# schematics.net
KiCad netlist of a schematic drawn in EasyEDA
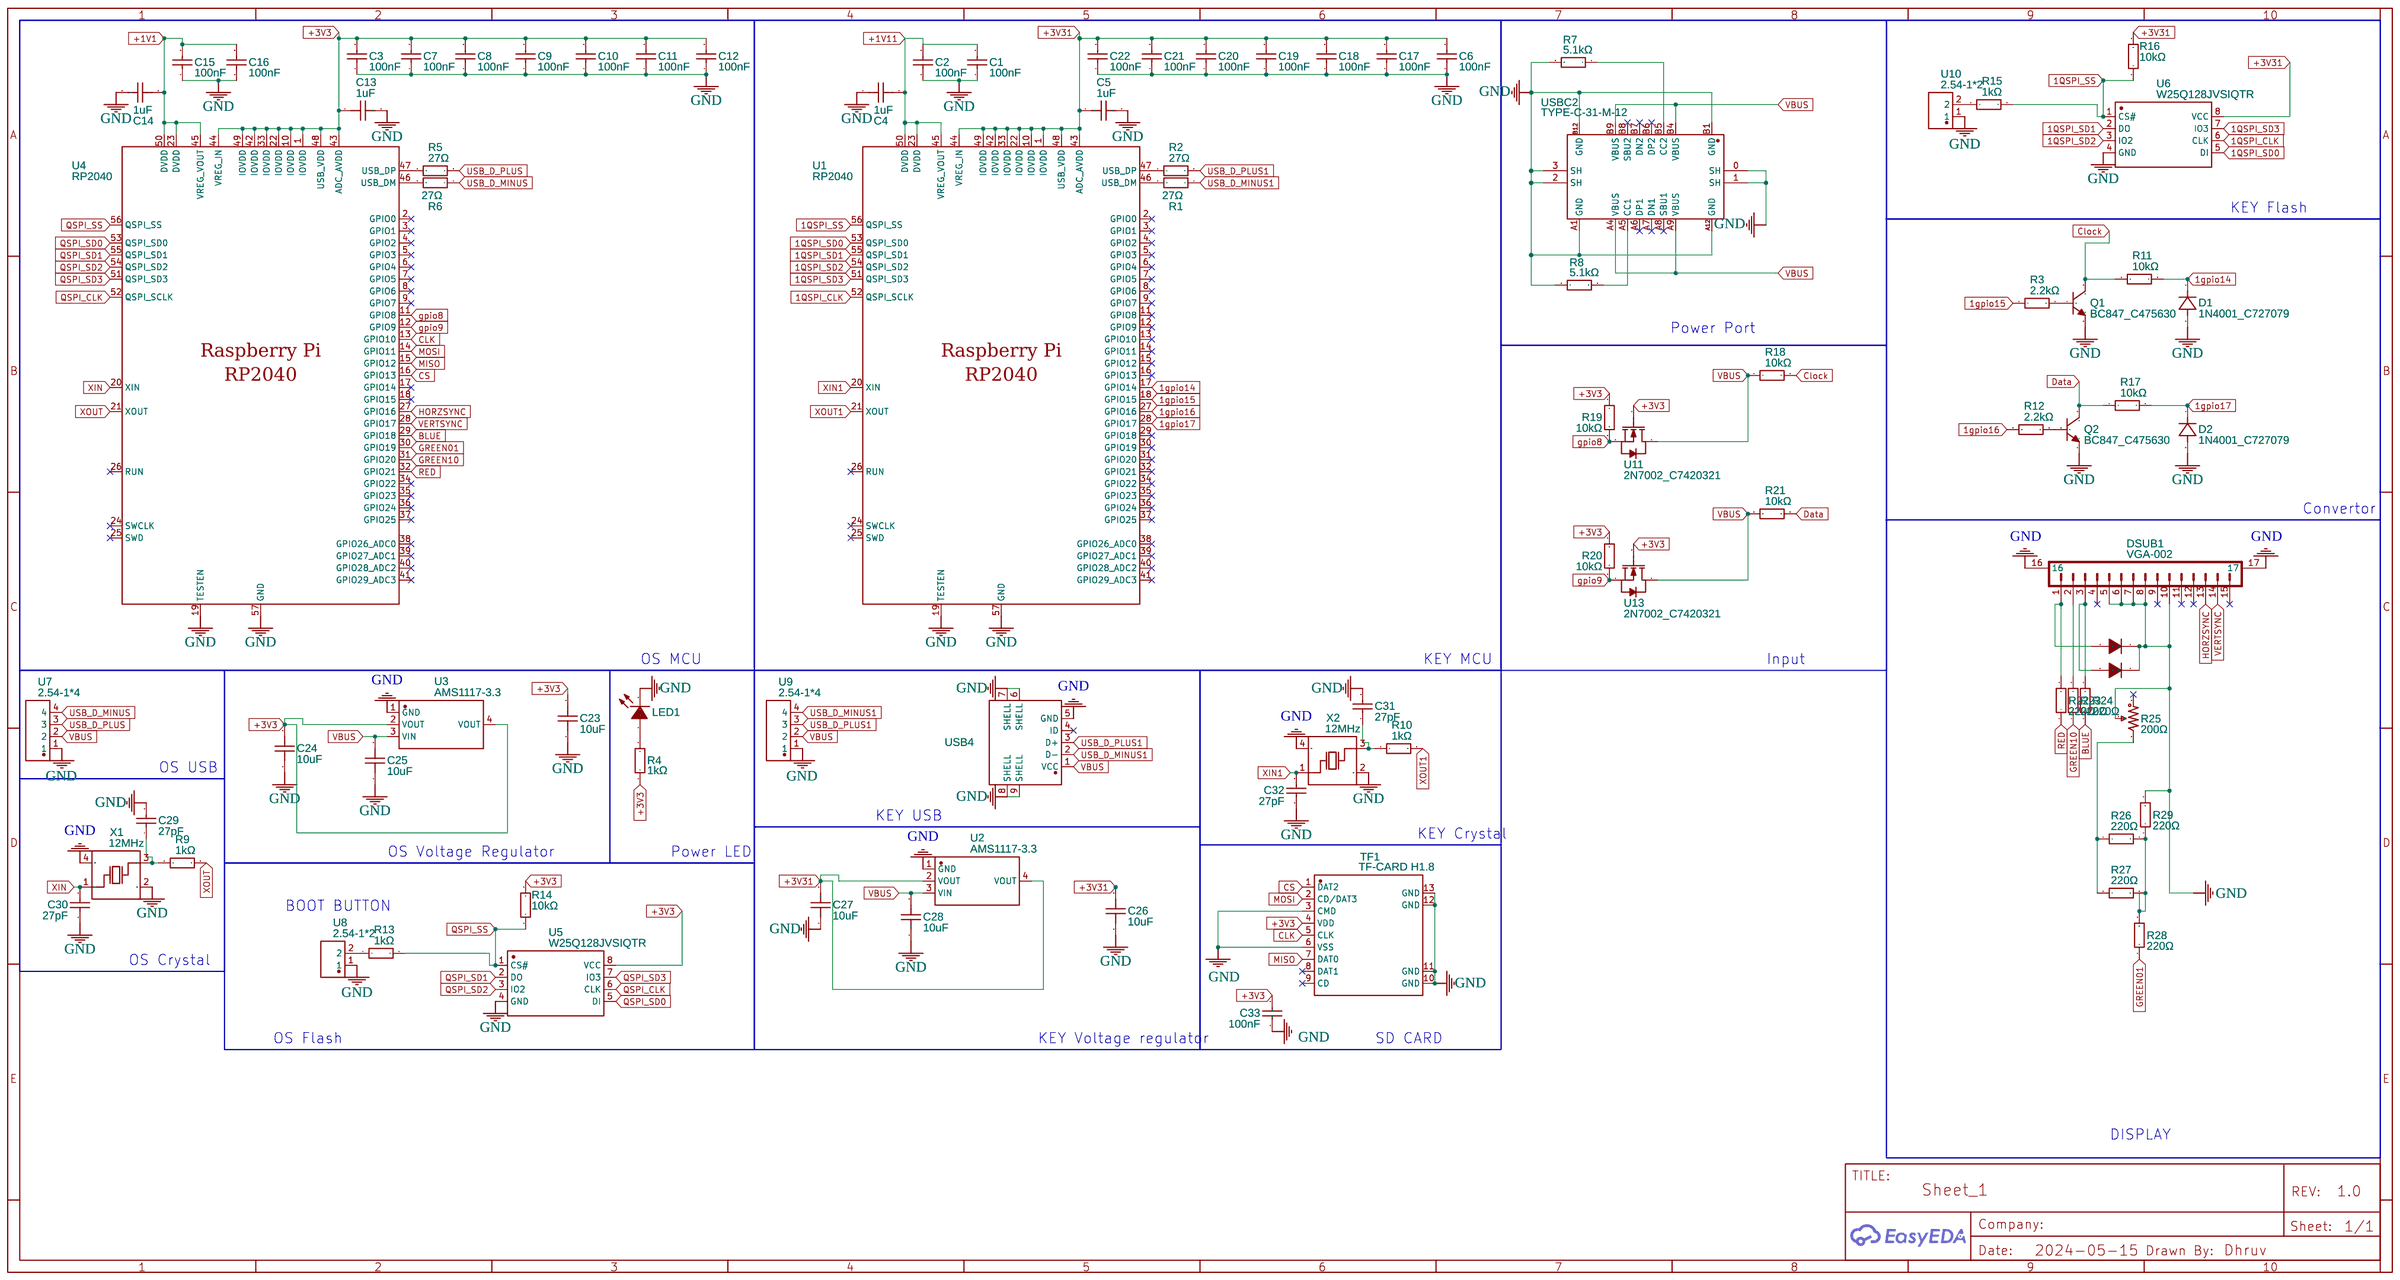
[diagram p0: schematic sheet]

(export (version "E")
  (design (tool "Eeschema 10.0.6"))
  (components
    (comp (ref "C1")
      (value "100nF")
      (fields
        (field (name "Manufacturer Part") "CL05B104KO5NNNC")
        (field (name "Manufacturer") "SAMSUNG(三星)")
      )
      (libsource (lib "") (part "CL05B104KO5NNNC_1"))
    )
    (comp (ref "C2")
      (value "100nF")
      (fields
        (field (name "Manufacturer Part") "CL05B104KO5NNNC")
        (field (name "Manufacturer") "SAMSUNG(三星)")
      )
      (libsource (lib "") (part "CL05B104KO5NNNC_1"))
    )
    (comp (ref "C3")
      (value "100nF")
      (fields
        (field (name "Manufacturer Part") "CL05B104KO5NNNC")
        (field (name "Manufacturer") "SAMSUNG(三星)")
      )
      (libsource (lib "") (part "CL05B104KO5NNNC_1"))
    )
    (comp (ref "C4")
      (value "1uF")
      (fields
        (field (name "Manufacturer Part") "CL05A105KA5NQNC")
        (field (name "Manufacturer") "SAMSUNG(三星)")
      )
      (libsource (lib "") (part "CL05A105KA5NQNC_1"))
    )
    (comp (ref "C5")
      (value "1uF")
      (fields
        (field (name "Manufacturer Part") "CL05A105KA5NQNC")
        (field (name "Manufacturer") "SAMSUNG(三星)")
      )
      (libsource (lib "") (part "CL05A105KA5NQNC"))
    )
    (comp (ref "C6")
      (value "100nF")
      (fields
        (field (name "Manufacturer Part") "CL05B104KO5NNNC")
        (field (name "Manufacturer") "SAMSUNG(三星)")
      )
      (libsource (lib "") (part "CL05B104KO5NNNC_1"))
    )
    (comp (ref "C7")
      (value "100nF")
      (fields
        (field (name "Manufacturer Part") "CL05B104KO5NNNC")
        (field (name "Manufacturer") "SAMSUNG(三星)")
      )
      (libsource (lib "") (part "CL05B104KO5NNNC_1"))
    )
    (comp (ref "C8")
      (value "100nF")
      (fields
        (field (name "Manufacturer Part") "CL05B104KO5NNNC")
        (field (name "Manufacturer") "SAMSUNG(三星)")
      )
      (libsource (lib "") (part "CL05B104KO5NNNC_1"))
    )
    (comp (ref "C9")
      (value "100nF")
      (fields
        (field (name "Manufacturer Part") "CL05B104KO5NNNC")
        (field (name "Manufacturer") "SAMSUNG(三星)")
      )
      (libsource (lib "") (part "CL05B104KO5NNNC_1"))
    )
    (comp (ref "C10")
      (value "100nF")
      (fields
        (field (name "Manufacturer Part") "CL05B104KO5NNNC")
        (field (name "Manufacturer") "SAMSUNG(三星)")
      )
      (libsource (lib "") (part "CL05B104KO5NNNC_1"))
    )
    (comp (ref "C11")
      (value "100nF")
      (fields
        (field (name "Manufacturer Part") "CL05B104KO5NNNC")
        (field (name "Manufacturer") "SAMSUNG(三星)")
      )
      (libsource (lib "") (part "CL05B104KO5NNNC_1"))
    )
    (comp (ref "C12")
      (value "100nF")
      (fields
        (field (name "Manufacturer Part") "CL05B104KO5NNNC")
        (field (name "Manufacturer") "SAMSUNG(三星)")
      )
      (libsource (lib "") (part "CL05B104KO5NNNC_1"))
    )
    (comp (ref "C13")
      (value "1uF")
      (fields
        (field (name "Manufacturer Part") "CL05A105KA5NQNC")
        (field (name "Manufacturer") "SAMSUNG(三星)")
      )
      (libsource (lib "") (part "CL05A105KA5NQNC"))
    )
    (comp (ref "C14")
      (value "1uF")
      (fields
        (field (name "Manufacturer Part") "CL05A105KA5NQNC")
        (field (name "Manufacturer") "SAMSUNG(三星)")
      )
      (libsource (lib "") (part "CL05A105KA5NQNC_1"))
    )
    (comp (ref "C15")
      (value "100nF")
      (fields
        (field (name "Manufacturer Part") "CL05B104KO5NNNC")
        (field (name "Manufacturer") "SAMSUNG(三星)")
      )
      (libsource (lib "") (part "CL05B104KO5NNNC_1"))
    )
    (comp (ref "C16")
      (value "100nF")
      (fields
        (field (name "Manufacturer Part") "CL05B104KO5NNNC")
        (field (name "Manufacturer") "SAMSUNG(三星)")
      )
      (libsource (lib "") (part "CL05B104KO5NNNC_1"))
    )
    (comp (ref "C17")
      (value "100nF")
      (fields
        (field (name "Manufacturer Part") "CL05B104KO5NNNC")
        (field (name "Manufacturer") "SAMSUNG(三星)")
      )
      (libsource (lib "") (part "CL05B104KO5NNNC_1"))
    )
    (comp (ref "C18")
      (value "100nF")
      (fields
        (field (name "Manufacturer Part") "CL05B104KO5NNNC")
        (field (name "Manufacturer") "SAMSUNG(三星)")
      )
      (libsource (lib "") (part "CL05B104KO5NNNC_1"))
    )
    (comp (ref "C19")
      (value "100nF")
      (fields
        (field (name "Manufacturer Part") "CL05B104KO5NNNC")
        (field (name "Manufacturer") "SAMSUNG(三星)")
      )
      (libsource (lib "") (part "CL05B104KO5NNNC_1"))
    )
    (comp (ref "C20")
      (value "100nF")
      (fields
        (field (name "Manufacturer Part") "CL05B104KO5NNNC")
        (field (name "Manufacturer") "SAMSUNG(三星)")
      )
      (libsource (lib "") (part "CL05B104KO5NNNC_1"))
    )
    (comp (ref "C21")
      (value "100nF")
      (fields
        (field (name "Manufacturer Part") "CL05B104KO5NNNC")
        (field (name "Manufacturer") "SAMSUNG(三星)")
      )
      (libsource (lib "") (part "CL05B104KO5NNNC_1"))
    )
    (comp (ref "C22")
      (value "100nF")
      (fields
        (field (name "Manufacturer Part") "CL05B104KO5NNNC")
        (field (name "Manufacturer") "SAMSUNG(三星)")
      )
      (libsource (lib "") (part "CL05B104KO5NNNC_1"))
    )
    (comp (ref "C23")
      (value "10uF")
      (fields
        (field (name "Manufacturer Part") "CL10A106KP8NNNC")
        (field (name "Manufacturer") "SAMSUNG(三星)")
      )
      (libsource (lib "") (part "CL10A106KP8NNNC"))
    )
    (comp (ref "C24")
      (value "10uF")
      (fields
        (field (name "Manufacturer Part") "CL10A106KP8NNNC")
        (field (name "Manufacturer") "SAMSUNG(三星)")
      )
      (libsource (lib "") (part "CL10A106KP8NNNC"))
    )
    (comp (ref "C25")
      (value "10uF")
      (fields
        (field (name "Manufacturer Part") "CL10A106KP8NNNC")
        (field (name "Manufacturer") "SAMSUNG(三星)")
      )
      (libsource (lib "") (part "CL10A106KP8NNNC"))
    )
    (comp (ref "C26")
      (value "10uF")
      (fields
        (field (name "Manufacturer Part") "CL10A106KP8NNNC")
        (field (name "Manufacturer") "SAMSUNG(三星)")
      )
      (libsource (lib "") (part "CL10A106KP8NNNC"))
    )
    (comp (ref "C27")
      (value "10uF")
      (fields
        (field (name "Manufacturer Part") "CL10A106KP8NNNC")
        (field (name "Manufacturer") "SAMSUNG(三星)")
      )
      (libsource (lib "") (part "CL10A106KP8NNNC"))
    )
    (comp (ref "C28")
      (value "10uF")
      (fields
        (field (name "Manufacturer Part") "CL10A106KP8NNNC")
        (field (name "Manufacturer") "SAMSUNG(三星)")
      )
      (libsource (lib "") (part "CL10A106KP8NNNC"))
    )
    (comp (ref "C29")
      (value "27pF")
      (fields
        (field (name "Manufacturer Part") "CC0603JRNPO9BN270")
        (field (name "Manufacturer") "YAGEO(国巨)")
      )
      (libsource (lib "") (part "CC0603JRNPO9BN270_1"))
    )
    (comp (ref "C30")
      (value "27pF")
      (fields
        (field (name "Manufacturer Part") "CC0603JRNPO9BN270")
        (field (name "Manufacturer") "YAGEO(国巨)")
      )
      (libsource (lib "") (part "CC0603JRNPO9BN270"))
    )
    (comp (ref "C31")
      (value "27pF")
      (fields
        (field (name "Manufacturer Part") "CC0603JRNPO9BN270")
        (field (name "Manufacturer") "YAGEO(国巨)")
      )
      (libsource (lib "") (part "CC0603JRNPO9BN270_1"))
    )
    (comp (ref "C32")
      (value "27pF")
      (fields
        (field (name "Manufacturer Part") "CC0603JRNPO9BN270")
        (field (name "Manufacturer") "YAGEO(国巨)")
      )
      (libsource (lib "") (part "CC0603JRNPO9BN270"))
    )
    (comp (ref "C33")
      (value "100nF")
      (fields
        (field (name "Manufacturer Part") "CL05B104KO5NNNC")
        (field (name "Manufacturer") "SAMSUNG(三星)")
      )
      (libsource (lib "") (part "CL05B104KO5NNNC"))
    )
    (comp (ref "D1")
      (value "1N4001_C727079")
      (fields (field (name "Manufacturer Part") "1N4001") (field (name "Manufacturer") "TWGMC(台湾迪嘉)"))
      (libsource (lib "") (part "1N4001_C727079"))
    )
    (comp (ref "D2")
      (value "1N4001_C727079")
      (fields (field (name "Manufacturer Part") "1N4001") (field (name "Manufacturer") "TWGMC(台湾迪嘉)"))
      (libsource (lib "") (part "1N4001_C727079"))
    )
    (comp (ref "D3")
      (value "1N4148WS T4")
      (fields (field (name "Manufacturer Part") "1N4148WS") (field (name "Manufacturer") "CJ(江苏长电/长晶)"))
      (libsource (lib "") (part "1N4148WS T4"))
    )
    (comp (ref "D4")
      (value "1N4148WS T4")
      (fields (field (name "Manufacturer Part") "1N4148WS") (field (name "Manufacturer") "CJ(江苏长电/长晶)"))
      (libsource (lib "") (part "1N4148WS T4"))
    )
    (comp (ref "DSUB1")
      (value "VGA-002")
      (fields (field (name "Manufacturer") "BOOMELE(博穆精密)"))
      (libsource (lib "") (part "VGA-002"))
    )
    (comp (ref "LED1")
      (value "0603White light_C2290")
      (fields (field (name "Manufacturer Part") "KT-0603白灯") (field (name "Manufacturer") "KENTO"))
      (libsource (lib "") (part "0603White light_C2290"))
    )
    (comp (ref "Q1")
      (value "BC847_C475630")
      (fields (field (name "Manufacturer Part") "BC847") (field (name "Manufacturer") "SHIKUES(时科)"))
      (libsource (lib "") (part "BC847_C475630"))
    )
    (comp (ref "Q2")
      (value "BC847_C475630")
      (fields (field (name "Manufacturer Part") "BC847") (field (name "Manufacturer") "SHIKUES(时科)"))
      (libsource (lib "") (part "BC847_C475630"))
    )
    (comp (ref "R1")
      (value "27Ω")
      (fields
        (field (name "Manufacturer Part") "0805W8F270JT5E")
        (field (name "Manufacturer") "UNI-ROYAL(厚声)")
      )
      (libsource (lib "") (part "0805W8F270JT5E"))
    )
    (comp (ref "R2")
      (value "27Ω")
      (fields
        (field (name "Manufacturer Part") "0805W8F270JT5E")
        (field (name "Manufacturer") "UNI-ROYAL(厚声)")
      )
      (libsource (lib "") (part "0805W8F270JT5E_1"))
    )
    (comp (ref "R3")
      (value "2.2kΩ")
      (fields
        (field (name "Manufacturer Part") "0402WGF2201TCE")
        (field (name "Manufacturer") "UNI-ROYAL(厚声)")
      )
      (libsource (lib "") (part "0402WGF2201TCE"))
    )
    (comp (ref "R4")
      (value "1kΩ")
      (fields
        (field (name "Manufacturer Part") "0402WGF1001TCE")
        (field (name "Manufacturer") "UNI-ROYAL(厚声)")
      )
      (libsource (lib "") (part "0402WGF1001TCE_1"))
    )
    (comp (ref "R5")
      (value "27Ω")
      (fields
        (field (name "Manufacturer Part") "0805W8F270JT5E")
        (field (name "Manufacturer") "UNI-ROYAL(厚声)")
      )
      (libsource (lib "") (part "0805W8F270JT5E_1"))
    )
    (comp (ref "R6")
      (value "27Ω")
      (fields
        (field (name "Manufacturer Part") "0805W8F270JT5E")
        (field (name "Manufacturer") "UNI-ROYAL(厚声)")
      )
      (libsource (lib "") (part "0805W8F270JT5E"))
    )
    (comp (ref "R7")
      (value "5.1kΩ")
      (fields (field (name "Manufacturer Part") "RTT02512JTH") (field (name "Manufacturer") "RALEC(旺诠)"))
      (libsource (lib "") (part "RTT02512JTH_1"))
    )
    (comp (ref "R8")
      (value "5.1kΩ")
      (fields (field (name "Manufacturer Part") "RTT02512JTH") (field (name "Manufacturer") "RALEC(旺诠)"))
      (libsource (lib "") (part "RTT02512JTH"))
    )
    (comp (ref "R9")
      (value "1kΩ")
      (fields
        (field (name "Manufacturer Part") "0402WGF1001TCE")
        (field (name "Manufacturer") "UNI-ROYAL(厚声)")
      )
      (libsource (lib "") (part "0402WGF1001TCE"))
    )
    (comp (ref "R10")
      (value "1kΩ")
      (fields
        (field (name "Manufacturer Part") "0402WGF1001TCE")
        (field (name "Manufacturer") "UNI-ROYAL(厚声)")
      )
      (libsource (lib "") (part "0402WGF1001TCE"))
    )
    (comp (ref "R11")
      (value "10kΩ")
      (fields
        (field (name "Manufacturer Part") "0402WGF1002TCE")
        (field (name "Manufacturer") "UNI-ROYAL(厚声)")
      )
      (libsource (lib "") (part "0402WGF1002TCE"))
    )
    (comp (ref "R12")
      (value "2.2kΩ")
      (fields
        (field (name "Manufacturer Part") "0402WGF2201TCE")
        (field (name "Manufacturer") "UNI-ROYAL(厚声)")
      )
      (libsource (lib "") (part "0402WGF2201TCE"))
    )
    (comp (ref "R13")
      (value "1kΩ")
      (fields
        (field (name "Manufacturer Part") "0402WGF1001TCE")
        (field (name "Manufacturer") "UNI-ROYAL(厚声)")
      )
      (libsource (lib "") (part "0402WGF1001TCE"))
    )
    (comp (ref "R14")
      (value "10kΩ")
      (fields
        (field (name "Manufacturer Part") "0402WGF1002TCE")
        (field (name "Manufacturer") "UNI-ROYAL(厚声)")
      )
      (libsource (lib "") (part "0402WGF1002TCE_1"))
    )
    (comp (ref "R15")
      (value "1kΩ")
      (fields
        (field (name "Manufacturer Part") "0402WGF1001TCE")
        (field (name "Manufacturer") "UNI-ROYAL(厚声)")
      )
      (libsource (lib "") (part "0402WGF1001TCE"))
    )
    (comp (ref "R16")
      (value "10kΩ")
      (fields
        (field (name "Manufacturer Part") "0402WGF1002TCE")
        (field (name "Manufacturer") "UNI-ROYAL(厚声)")
      )
      (libsource (lib "") (part "0402WGF1002TCE_1"))
    )
    (comp (ref "R17")
      (value "10kΩ")
      (fields
        (field (name "Manufacturer Part") "0402WGF1002TCE")
        (field (name "Manufacturer") "UNI-ROYAL(厚声)")
      )
      (libsource (lib "") (part "0402WGF1002TCE"))
    )
    (comp (ref "R18")
      (value "10kΩ")
      (fields
        (field (name "Manufacturer Part") "0402WGF1002TCE")
        (field (name "Manufacturer") "UNI-ROYAL(厚声)")
      )
      (libsource (lib "") (part "0402WGF1002TCE"))
    )
    (comp (ref "R19")
      (value "10kΩ")
      (fields
        (field (name "Manufacturer Part") "0402WGF1002TCE")
        (field (name "Manufacturer") "UNI-ROYAL(厚声)")
      )
      (libsource (lib "") (part "0402WGF1002TCE_2"))
    )
    (comp (ref "R20")
      (value "10kΩ")
      (fields
        (field (name "Manufacturer Part") "0402WGF1002TCE")
        (field (name "Manufacturer") "UNI-ROYAL(厚声)")
      )
      (libsource (lib "") (part "0402WGF1002TCE_2"))
    )
    (comp (ref "R21")
      (value "10kΩ")
      (fields
        (field (name "Manufacturer Part") "0402WGF1002TCE")
        (field (name "Manufacturer") "UNI-ROYAL(厚声)")
      )
      (libsource (lib "") (part "0402WGF1002TCE"))
    )
    (comp (ref "R22")
      (value "220Ω")
      (fields
        (field (name "Manufacturer Part") "0402WGF2200TCE")
        (field (name "Manufacturer") "UNI-ROYAL(厚声)")
      )
      (libsource (lib "") (part "0402WGF2200TCE"))
    )
    (comp (ref "R23")
      (value "220Ω")
      (fields
        (field (name "Manufacturer Part") "0402WGF2200TCE")
        (field (name "Manufacturer") "UNI-ROYAL(厚声)")
      )
      (libsource (lib "") (part "0402WGF2200TCE"))
    )
    (comp (ref "R24")
      (value "220Ω")
      (fields
        (field (name "Manufacturer Part") "0402WGF2200TCE")
        (field (name "Manufacturer") "UNI-ROYAL(厚声)")
      )
      (libsource (lib "") (part "0402WGF2200TCE"))
    )
    (comp (ref "R25")
      (value "200Ω")
      (fields (field (name "Manufacturer Part") "3266W-1-201") (field (name "Manufacturer") "BOCHEN(博晨)"))
      (libsource (lib "") (part "3266W-1-201"))
    )
    (comp (ref "R26")
      (value "220Ω")
      (fields
        (field (name "Manufacturer Part") "0402WGF2200TCE")
        (field (name "Manufacturer") "UNI-ROYAL(厚声)")
      )
      (libsource (lib "") (part "0402WGF2200TCE_1"))
    )
    (comp (ref "R27")
      (value "220Ω")
      (fields
        (field (name "Manufacturer Part") "0402WGF2200TCE")
        (field (name "Manufacturer") "UNI-ROYAL(厚声)")
      )
      (libsource (lib "") (part "0402WGF2200TCE_1"))
    )
    (comp (ref "R28")
      (value "220Ω")
      (fields
        (field (name "Manufacturer Part") "0402WGF2200TCE")
        (field (name "Manufacturer") "UNI-ROYAL(厚声)")
      )
      (libsource (lib "") (part "0402WGF2200TCE"))
    )
    (comp (ref "R29")
      (value "220Ω")
      (fields
        (field (name "Manufacturer Part") "0402WGF2200TCE")
        (field (name "Manufacturer") "UNI-ROYAL(厚声)")
      )
      (libsource (lib "") (part "0402WGF2200TCE"))
    )
    (comp (ref "TF1")
      (value "TF-CARD H1.8")
      (fields (field (name "Manufacturer") "SHOU HAN(首韩)"))
      (libsource (lib "") (part "TF-CARD H1.8"))
    )
    (comp (ref "U1")
      (value "RP2040")
      (fields (field (name "Manufacturer") "Raspberry Pi(树莓派)"))
      (libsource (lib "") (part "RP2040"))
    )
    (comp (ref "U2")
      (value "AMS1117-3.3")
      (fields (field (name "Manufacturer") "AMS"))
      (libsource (lib "") (part "AMS1117-3.3"))
    )
    (comp (ref "U3")
      (value "AMS1117-3.3")
      (fields (field (name "Manufacturer") "AMS"))
      (libsource (lib "") (part "AMS1117-3.3"))
    )
    (comp (ref "U4")
      (value "RP2040")
      (fields (field (name "Manufacturer") "Raspberry Pi(树莓派)"))
      (libsource (lib "") (part "RP2040"))
    )
    (comp (ref "U5")
      (value "W25Q128JVSIQTR")
      (fields (field (name "Manufacturer Part") "W25Q128JVSIQ") (field (name "Manufacturer") "WINBOND(华邦)"))
      (libsource (lib "") (part "W25Q128JVSIQTR"))
    )
    (comp (ref "U6")
      (value "W25Q128JVSIQTR")
      (fields (field (name "Manufacturer Part") "W25Q128JVSIQ") (field (name "Manufacturer") "WINBOND(华邦)"))
      (libsource (lib "") (part "W25Q128JVSIQTR"))
    )
    (comp (ref "U7")
      (value "2.54-1*4")
      (fields (field (name "Manufacturer") "ZHOURI(洲日)"))
      (libsource (lib "") (part "2.54-1*4"))
    )
    (comp (ref "U8")
      (value "2.54-1*2")
      (fields (field (name "Manufacturer") "ZHOURI(洲日)"))
      (libsource (lib "") (part "2.54-1*2"))
    )
    (comp (ref "U9")
      (value "2.54-1*4")
      (fields (field (name "Manufacturer") "ZHOURI(洲日)"))
      (libsource (lib "") (part "2.54-1*4"))
    )
    (comp (ref "U10")
      (value "2.54-1*2")
      (fields (field (name "Manufacturer") "ZHOURI(洲日)"))
      (libsource (lib "") (part "2.54-1*2"))
    )
    (comp (ref "U11")
      (value "2N7002_C7420321")
      (fields (field (name "Manufacturer Part") "2N7002") (field (name "Manufacturer") "宏迦橙"))
      (libsource (lib "") (part "2N7002_C7420321"))
    )
    (comp (ref "U13")
      (value "2N7002_C7420321")
      (fields (field (name "Manufacturer Part") "2N7002") (field (name "Manufacturer") "宏迦橙"))
      (libsource (lib "") (part "2N7002_C7420321"))
    )
    (comp (ref "USB4")
      (value "U224-051N-3GRA035")
      (fields (field (name "Manufacturer") "XKB Connectivity(中国星坤)"))
      (libsource (lib "") (part "U224-051N-3GRA035"))
    )
    (comp (ref "USBC2")
      (value "TYPE-C-31-M-12")
      (fields (field (name "Manufacturer") "韩国韩荣"))
      (libsource (lib "") (part "TYPE-C-31-M-12"))
    )
    (comp (ref "X1")
      (value "12MHz")
      (fields (field (name "Manufacturer Part") "X322512MSB4SI") (field (name "Manufacturer") "YXC(扬兴晶振)"))
      (libsource (lib "") (part "X322512MSB4SI"))
    )
    (comp (ref "X2")
      (value "12MHz")
      (fields (field (name "Manufacturer Part") "X322512MSB4SI") (field (name "Manufacturer") "YXC(扬兴晶振)"))
      (libsource (lib "") (part "X322512MSB4SI"))
    )
  )
  (nets
    (net (code "1") (name "+1V1") (class "Default")
      (node (ref "C14") (pin "2") (pinfunction "2_2") (pintype "unspecified"))
      (node (ref "C15") (pin "2") (pinfunction "2_2") (pintype "input"))
      (node (ref "C16") (pin "2") (pinfunction "2_2") (pintype "input"))
      (node (ref "U4") (pin "23") (pinfunction "DVDD_23") (pintype "bidirectional"))
      (node (ref "U4") (pin "45") (pinfunction "VREG_VOUT_45") (pintype "bidirectional"))
      (node (ref "U4") (pin "50") (pinfunction "DVDD_50") (pintype "bidirectional"))
    )
    (net (code "2") (name "+1V11") (class "Default")
      (node (ref "C1") (pin "2") (pinfunction "2_2") (pintype "input"))
      (node (ref "C2") (pin "2") (pinfunction "2_2") (pintype "input"))
      (node (ref "C4") (pin "2") (pinfunction "2_2") (pintype "unspecified"))
      (node (ref "U1") (pin "23") (pinfunction "DVDD_23") (pintype "bidirectional"))
      (node (ref "U1") (pin "45") (pinfunction "VREG_VOUT_45") (pintype "bidirectional"))
      (node (ref "U1") (pin "50") (pinfunction "DVDD_50") (pintype "bidirectional"))
    )
    (net (code "3") (name "+3V3") (class "Default")
      (node (ref "C10") (pin "2") (pinfunction "2_2") (pintype "input"))
      (node (ref "C11") (pin "2") (pinfunction "2_2") (pintype "input"))
      (node (ref "C12") (pin "2") (pinfunction "2_2") (pintype "input"))
      (node (ref "C13") (pin "1") (pinfunction "1_1") (pintype "unspecified"))
      (node (ref "C23") (pin "2") (pinfunction "2_2") (pintype "unspecified"))
      (node (ref "C24") (pin "2") (pinfunction "2_2") (pintype "unspecified"))
      (node (ref "C3") (pin "2") (pinfunction "2_2") (pintype "input"))
      (node (ref "C33") (pin "1") (pinfunction "1_1") (pintype "input"))
      (node (ref "C7") (pin "2") (pinfunction "2_2") (pintype "input"))
      (node (ref "C8") (pin "2") (pinfunction "2_2") (pintype "input"))
      (node (ref "C9") (pin "2") (pinfunction "2_2") (pintype "input"))
      (node (ref "R14") (pin "2") (pinfunction "2_2") (pintype "input"))
      (node (ref "R19") (pin "1") (pinfunction "1_1") (pintype "input"))
      (node (ref "R20") (pin "1") (pinfunction "1_1") (pintype "input"))
      (node (ref "R4") (pin "1") (pinfunction "1_1") (pintype "input"))
      (node (ref "TF1") (pin "4") (pinfunction "VDD_4") (pintype "unspecified"))
      (node (ref "U11") (pin "1") (pinfunction "G_1") (pintype "unspecified"))
      (node (ref "U13") (pin "1") (pinfunction "G_1") (pintype "unspecified"))
      (node (ref "U3") (pin "2") (pinfunction "VOUT_2") (pintype "unspecified"))
      (node (ref "U3") (pin "4") (pinfunction "VOUT_4") (pintype "unspecified"))
      (node (ref "U4") (pin "1") (pinfunction "IOVDD_1") (pintype "bidirectional"))
      (node (ref "U4") (pin "10") (pinfunction "IOVDD_10") (pintype "bidirectional"))
      (node (ref "U4") (pin "22") (pinfunction "IOVDD_22") (pintype "bidirectional"))
      (node (ref "U4") (pin "33") (pinfunction "IOVDD_33") (pintype "bidirectional"))
      (node (ref "U4") (pin "42") (pinfunction "IOVDD_42") (pintype "bidirectional"))
      (node (ref "U4") (pin "43") (pinfunction "ADC_AVDD_43") (pintype "bidirectional"))
      (node (ref "U4") (pin "44") (pinfunction "VREG_IN_44") (pintype "bidirectional"))
      (node (ref "U4") (pin "48") (pinfunction "USB_VDD_48") (pintype "bidirectional"))
      (node (ref "U4") (pin "49") (pinfunction "IOVDD_49") (pintype "bidirectional"))
      (node (ref "U5") (pin "8") (pinfunction "VCC_8") (pintype "unspecified"))
    )
    (net (code "4") (name "+3V31") (class "Default")
      (node (ref "C17") (pin "2") (pinfunction "2_2") (pintype "input"))
      (node (ref "C18") (pin "2") (pinfunction "2_2") (pintype "input"))
      (node (ref "C19") (pin "2") (pinfunction "2_2") (pintype "input"))
      (node (ref "C20") (pin "2") (pinfunction "2_2") (pintype "input"))
      (node (ref "C21") (pin "2") (pinfunction "2_2") (pintype "input"))
      (node (ref "C22") (pin "2") (pinfunction "2_2") (pintype "input"))
      (node (ref "C26") (pin "2") (pinfunction "2_2") (pintype "unspecified"))
      (node (ref "C27") (pin "2") (pinfunction "2_2") (pintype "unspecified"))
      (node (ref "C5") (pin "1") (pinfunction "1_1") (pintype "unspecified"))
      (node (ref "C6") (pin "2") (pinfunction "2_2") (pintype "input"))
      (node (ref "R16") (pin "2") (pinfunction "2_2") (pintype "input"))
      (node (ref "U1") (pin "1") (pinfunction "IOVDD_1") (pintype "bidirectional"))
      (node (ref "U1") (pin "10") (pinfunction "IOVDD_10") (pintype "bidirectional"))
      (node (ref "U1") (pin "22") (pinfunction "IOVDD_22") (pintype "bidirectional"))
      (node (ref "U1") (pin "33") (pinfunction "IOVDD_33") (pintype "bidirectional"))
      (node (ref "U1") (pin "42") (pinfunction "IOVDD_42") (pintype "bidirectional"))
      (node (ref "U1") (pin "43") (pinfunction "ADC_AVDD_43") (pintype "bidirectional"))
      (node (ref "U1") (pin "44") (pinfunction "VREG_IN_44") (pintype "bidirectional"))
      (node (ref "U1") (pin "48") (pinfunction "USB_VDD_48") (pintype "bidirectional"))
      (node (ref "U1") (pin "49") (pinfunction "IOVDD_49") (pintype "bidirectional"))
      (node (ref "U2") (pin "2") (pinfunction "VOUT_2") (pintype "unspecified"))
      (node (ref "U2") (pin "4") (pinfunction "VOUT_4") (pintype "unspecified"))
      (node (ref "U6") (pin "8") (pinfunction "VCC_8") (pintype "unspecified"))
    )
    (net (code "5") (name "1QSPI_CLK") (class "Default")
      (node (ref "U1") (pin "52") (pinfunction "QSPI_SCLK_52") (pintype "output"))
      (node (ref "U6") (pin "6") (pinfunction "CLK_6") (pintype "unspecified"))
    )
    (net (code "6") (name "1QSPI_SD0") (class "Default")
      (node (ref "U1") (pin "53") (pinfunction "QSPI_SD0_53") (pintype "bidirectional"))
      (node (ref "U6") (pin "5") (pinfunction "DI_5") (pintype "unspecified"))
    )
    (net (code "7") (name "1QSPI_SD1") (class "Default")
      (node (ref "U1") (pin "55") (pinfunction "QSPI_SD1_55") (pintype "bidirectional"))
      (node (ref "U6") (pin "2") (pinfunction "DO_2") (pintype "unspecified"))
    )
    (net (code "8") (name "1QSPI_SD2") (class "Default")
      (node (ref "U1") (pin "54") (pinfunction "QSPI_SD2_54") (pintype "bidirectional"))
      (node (ref "U6") (pin "3") (pinfunction "IO2_3") (pintype "unspecified"))
    )
    (net (code "9") (name "1QSPI_SD3") (class "Default")
      (node (ref "U1") (pin "51") (pinfunction "QSPI_SD3_51") (pintype "bidirectional"))
      (node (ref "U6") (pin "7") (pinfunction "IO3_7") (pintype "unspecified"))
    )
    (net (code "10") (name "1QSPI_SS") (class "Default")
      (node (ref "R15") (pin "2") (pinfunction "2_2") (pintype "input"))
      (node (ref "R16") (pin "1") (pinfunction "1_1") (pintype "input"))
      (node (ref "U1") (pin "56") (pinfunction "QSPI_SS_56") (pintype "bidirectional"))
      (node (ref "U6") (pin "1") (pinfunction "CS#_1") (pintype "unspecified"))
    )
    (net (code "11") (name "1gpio14") (class "Default")
      (node (ref "D1") (pin "1") (pinfunction "K_1") (pintype "unspecified"))
      (node (ref "R11") (pin "2") (pinfunction "2_2") (pintype "input"))
      (node (ref "U1") (pin "17") (pinfunction "GPIO14_17") (pintype "bidirectional"))
    )
    (net (code "12") (name "1gpio15") (class "Default")
      (node (ref "R3") (pin "1") (pinfunction "1_1") (pintype "input"))
      (node (ref "U1") (pin "18") (pinfunction "GPIO15_18") (pintype "bidirectional"))
    )
    (net (code "13") (name "1gpio16") (class "Default")
      (node (ref "R12") (pin "1") (pinfunction "1_1") (pintype "input"))
      (node (ref "U1") (pin "27") (pinfunction "GPIO16_27") (pintype "bidirectional"))
    )
    (net (code "14") (name "1gpio17") (class "Default")
      (node (ref "D2") (pin "1") (pinfunction "K_1") (pintype "unspecified"))
      (node (ref "R17") (pin "2") (pinfunction "2_2") (pintype "input"))
      (node (ref "U1") (pin "28") (pinfunction "GPIO17_28") (pintype "bidirectional"))
    )
    (net (code "15") (name "BLUE") (class "Default")
      (node (ref "R24") (pin "1") (pinfunction "1_1") (pintype "input"))
      (node (ref "U4") (pin "29") (pinfunction "GPIO18_29") (pintype "bidirectional"))
    )
    (net (code "16") (name "CLK") (class "Default")
      (node (ref "TF1") (pin "5") (pinfunction "CLK_5") (pintype "unspecified"))
      (node (ref "U4") (pin "13") (pinfunction "GPIO10_13") (pintype "bidirectional"))
    )
    (net (code "17") (name "CS") (class "Default")
      (node (ref "TF1") (pin "1") (pinfunction "DAT2_1") (pintype "unspecified"))
      (node (ref "U4") (pin "16") (pinfunction "GPIO13_16") (pintype "bidirectional"))
    )
    (net (code "18") (name "Clock") (class "Default")
      (node (ref "Q1") (pin "3") (pinfunction "C_3") (pintype "unspecified"))
      (node (ref "R11") (pin "1") (pinfunction "1_1") (pintype "input"))
      (node (ref "R18") (pin "2") (pinfunction "2_2") (pintype "input"))
    )
    (net (code "19") (name "Data") (class "Default")
      (node (ref "Q2") (pin "3") (pinfunction "C_3") (pintype "unspecified"))
      (node (ref "R17") (pin "1") (pinfunction "1_1") (pintype "input"))
      (node (ref "R21") (pin "2") (pinfunction "2_2") (pintype "input"))
    )
    (net (code "20") (name "GND") (class "Default")
      (node (ref "C1") (pin "1") (pinfunction "1_1") (pintype "input"))
      (node (ref "C10") (pin "1") (pinfunction "1_1") (pintype "input"))
      (node (ref "C11") (pin "1") (pinfunction "1_1") (pintype "input"))
      (node (ref "C12") (pin "1") (pinfunction "1_1") (pintype "input"))
      (node (ref "C13") (pin "2") (pinfunction "2_2") (pintype "unspecified"))
      (node (ref "C14") (pin "1") (pinfunction "1_1") (pintype "unspecified"))
      (node (ref "C15") (pin "1") (pinfunction "1_1") (pintype "input"))
      (node (ref "C16") (pin "1") (pinfunction "1_1") (pintype "input"))
      (node (ref "C17") (pin "1") (pinfunction "1_1") (pintype "input"))
      (node (ref "C18") (pin "1") (pinfunction "1_1") (pintype "input"))
      (node (ref "C19") (pin "1") (pinfunction "1_1") (pintype "input"))
      (node (ref "C2") (pin "1") (pinfunction "1_1") (pintype "input"))
      (node (ref "C20") (pin "1") (pinfunction "1_1") (pintype "input"))
      (node (ref "C21") (pin "1") (pinfunction "1_1") (pintype "input"))
      (node (ref "C22") (pin "1") (pinfunction "1_1") (pintype "input"))
      (node (ref "C23") (pin "1") (pinfunction "1_1") (pintype "unspecified"))
      (node (ref "C24") (pin "1") (pinfunction "1_1") (pintype "unspecified"))
      (node (ref "C25") (pin "1") (pinfunction "1_1") (pintype "unspecified"))
      (node (ref "C26") (pin "1") (pinfunction "1_1") (pintype "unspecified"))
      (node (ref "C27") (pin "1") (pinfunction "1_1") (pintype "unspecified"))
      (node (ref "C28") (pin "1") (pinfunction "1_1") (pintype "unspecified"))
      (node (ref "C29") (pin "2") (pinfunction "2_2") (pintype "input"))
      (node (ref "C3") (pin "1") (pinfunction "1_1") (pintype "input"))
      (node (ref "C30") (pin "1") (pinfunction "1_1") (pintype "input"))
      (node (ref "C31") (pin "2") (pinfunction "2_2") (pintype "input"))
      (node (ref "C32") (pin "1") (pinfunction "1_1") (pintype "input"))
      (node (ref "C33") (pin "2") (pinfunction "2_2") (pintype "input"))
      (node (ref "C4") (pin "1") (pinfunction "1_1") (pintype "unspecified"))
      (node (ref "C5") (pin "2") (pinfunction "2_2") (pintype "unspecified"))
      (node (ref "C6") (pin "1") (pinfunction "1_1") (pintype "input"))
      (node (ref "C7") (pin "1") (pinfunction "1_1") (pintype "input"))
      (node (ref "C8") (pin "1") (pinfunction "1_1") (pintype "input"))
      (node (ref "C9") (pin "1") (pinfunction "1_1") (pintype "input"))
      (node (ref "D1") (pin "2") (pinfunction "A_2") (pintype "unspecified"))
      (node (ref "D2") (pin "2") (pinfunction "A_2") (pintype "unspecified"))
      (node (ref "D3") (pin "1") (pinfunction "K_1") (pintype "unspecified"))
      (node (ref "D4") (pin "1") (pinfunction "K_1") (pintype "unspecified"))
      (node (ref "DSUB1") (pin "10") (pinfunction "10_10") (pintype "unspecified"))
      (node (ref "DSUB1") (pin "16") (pinfunction "16_16") (pintype "unspecified"))
      (node (ref "DSUB1") (pin "17") (pinfunction "17_17") (pintype "unspecified"))
      (node (ref "DSUB1") (pin "5") (pinfunction "5_5") (pintype "unspecified"))
      (node (ref "DSUB1") (pin "6") (pinfunction "6_6") (pintype "unspecified"))
      (node (ref "DSUB1") (pin "7") (pinfunction "7_7") (pintype "unspecified"))
      (node (ref "DSUB1") (pin "8") (pinfunction "8_8") (pintype "unspecified"))
      (node (ref "LED1") (pin "2") (pinfunction "K_2") (pintype "unspecified"))
      (node (ref "Q1") (pin "2") (pinfunction "E_2") (pintype "unspecified"))
      (node (ref "Q2") (pin "2") (pinfunction "E_2") (pintype "unspecified"))
      (node (ref "R25") (pin "2") (pinfunction "2_2") (pintype "unspecified"))
      (node (ref "R29") (pin "2") (pinfunction "2_2") (pintype "input"))
      (node (ref "R7") (pin "2") (pinfunction "2_2") (pintype "input"))
      (node (ref "R8") (pin "1") (pinfunction "1_1") (pintype "input"))
      (node (ref "TF1") (pin "10") (pinfunction "GND_10") (pintype "unspecified"))
      (node (ref "TF1") (pin "11") (pinfunction "GND_11") (pintype "unspecified"))
      (node (ref "TF1") (pin "12") (pinfunction "GND_12") (pintype "unspecified"))
      (node (ref "TF1") (pin "13") (pinfunction "GND_13") (pintype "unspecified"))
      (node (ref "TF1") (pin "3") (pinfunction "CMD_3") (pintype "unspecified"))
      (node (ref "TF1") (pin "6") (pinfunction "VSS_6") (pintype "unspecified"))
      (node (ref "U1") (pin "19") (pinfunction "TESTEN_19") (pintype "unspecified"))
      (node (ref "U1") (pin "57") (pinfunction "GND_57") (pintype "bidirectional"))
      (node (ref "U10") (pin "1") (pinfunction "1_1") (pintype "unspecified"))
      (node (ref "U2") (pin "1") (pinfunction "GND_1") (pintype "unspecified"))
      (node (ref "U3") (pin "1") (pinfunction "GND_1") (pintype "unspecified"))
      (node (ref "U4") (pin "19") (pinfunction "TESTEN_19") (pintype "unspecified"))
      (node (ref "U4") (pin "57") (pinfunction "GND_57") (pintype "bidirectional"))
      (node (ref "U5") (pin "4") (pinfunction "GND_4") (pintype "unspecified"))
      (node (ref "U6") (pin "4") (pinfunction "GND_4") (pintype "unspecified"))
      (node (ref "U7") (pin "1") (pinfunction "1_1") (pintype "unspecified"))
      (node (ref "U8") (pin "1") (pinfunction "1_1") (pintype "unspecified"))
      (node (ref "U9") (pin "1") (pinfunction "1_1") (pintype "unspecified"))
      (node (ref "USB4") (pin "5") (pinfunction "GND_5") (pintype "unspecified"))
      (node (ref "USB4") (pin "6") (pinfunction "SHELL_6") (pintype "unspecified"))
      (node (ref "USB4") (pin "7") (pinfunction "SHELL_7") (pintype "unspecified"))
      (node (ref "USB4") (pin "8") (pinfunction "SHELL_8") (pintype "unspecified"))
      (node (ref "USB4") (pin "9") (pinfunction "SHELL_9") (pintype "unspecified"))
      (node (ref "USBC2") (pin "0") (pinfunction "SH_0") (pintype "unspecified"))
      (node (ref "USBC2") (pin "1") (pinfunction "SH_1") (pintype "unspecified"))
      (node (ref "USBC2") (pin "2") (pinfunction "SH_2") (pintype "unspecified"))
      (node (ref "USBC2") (pin "3") (pinfunction "SH_3") (pintype "unspecified"))
      (node (ref "USBC2") (pin "A1") (pinfunction "GND_A1") (pintype "unspecified"))
      (node (ref "USBC2") (pin "A12") (pinfunction "GND_A12") (pintype "unspecified"))
      (node (ref "USBC2") (pin "B1") (pinfunction "GND_B1") (pintype "unspecified"))
      (node (ref "USBC2") (pin "B12") (pinfunction "GND_B12") (pintype "unspecified"))
      (node (ref "X1") (pin "2") (pinfunction "GND_2") (pintype "unspecified"))
      (node (ref "X1") (pin "4") (pinfunction "GND_4") (pintype "unspecified"))
      (node (ref "X2") (pin "2") (pinfunction "GND_2") (pintype "unspecified"))
      (node (ref "X2") (pin "4") (pinfunction "GND_4") (pintype "unspecified"))
    )
    (net (code "21") (name "GREEN01") (class "Default")
      (node (ref "R28") (pin "1") (pinfunction "1_1") (pintype "input"))
      (node (ref "U4") (pin "30") (pinfunction "GPIO19_30") (pintype "bidirectional"))
    )
    (net (code "22") (name "GREEN10") (class "Default")
      (node (ref "R23") (pin "1") (pinfunction "1_1") (pintype "input"))
      (node (ref "U4") (pin "31") (pinfunction "GPIO20_31") (pintype "bidirectional"))
    )
    (net (code "23") (name "HORZSYNC") (class "Default")
      (node (ref "DSUB1") (pin "13") (pinfunction "13_13") (pintype "unspecified"))
      (node (ref "U4") (pin "27") (pinfunction "GPIO16_27") (pintype "bidirectional"))
    )
    (net (code "24") (name "MISO") (class "Default")
      (node (ref "TF1") (pin "7") (pinfunction "DAT0_7") (pintype "unspecified"))
      (node (ref "U4") (pin "15") (pinfunction "GPIO12_15") (pintype "bidirectional"))
    )
    (net (code "25") (name "MOSI") (class "Default")
      (node (ref "TF1") (pin "2") (pinfunction "CD/DAT3_2") (pintype "unspecified"))
      (node (ref "U4") (pin "14") (pinfunction "GPIO11_14") (pintype "bidirectional"))
    )
    (net (code "26") (name "Net-(D3-A)") (class "Default")
      (node (ref "D3") (pin "2") (pinfunction "A_2") (pintype "unspecified"))
      (node (ref "DSUB1") (pin "3") (pinfunction "3_3") (pintype "unspecified"))
      (node (ref "R24") (pin "2") (pinfunction "2_2") (pintype "input"))
    )
    (net (code "27") (name "Net-(D4-A)") (class "Default")
      (node (ref "D4") (pin "2") (pinfunction "A_2") (pintype "unspecified"))
      (node (ref "DSUB1") (pin "1") (pinfunction "1_1") (pintype "unspecified"))
      (node (ref "R22") (pin "2") (pinfunction "2_2") (pintype "input"))
    )
    (net (code "28") (name "Net-(DSUB1-Pad2)") (class "Default")
      (node (ref "DSUB1") (pin "2") (pinfunction "2_2") (pintype "unspecified"))
      (node (ref "R23") (pin "2") (pinfunction "2_2") (pintype "input"))
    )
    (net (code "29") (name "Net-(LED1-A)") (class "Default")
      (node (ref "LED1") (pin "1") (pinfunction "A_1") (pintype "unspecified"))
      (node (ref "R4") (pin "2") (pinfunction "2_2") (pintype "input"))
    )
    (net (code "30") (name "Net-(Q1-B)") (class "Default")
      (node (ref "Q1") (pin "1") (pinfunction "B_1") (pintype "unspecified"))
      (node (ref "R3") (pin "2") (pinfunction "2_2") (pintype "input"))
    )
    (net (code "31") (name "Net-(Q2-B)") (class "Default")
      (node (ref "Q2") (pin "1") (pinfunction "B_1") (pintype "unspecified"))
      (node (ref "R12") (pin "2") (pinfunction "2_2") (pintype "input"))
    )
    (net (code "32") (name "Net-(R13-Pad1)") (class "Default")
      (node (ref "R13") (pin "1") (pinfunction "1_1") (pintype "input"))
      (node (ref "U8") (pin "2") (pinfunction "2_2") (pintype "unspecified"))
    )
    (net (code "33") (name "Net-(R15-Pad1)") (class "Default")
      (node (ref "R15") (pin "1") (pinfunction "1_1") (pintype "input"))
      (node (ref "U10") (pin "2") (pinfunction "2_2") (pintype "unspecified"))
    )
    (net (code "34") (name "Net-(R25-Pad3)") (class "Default")
      (node (ref "R25") (pin "3") (pinfunction "3_3") (pintype "unspecified"))
      (node (ref "R26") (pin "1") (pinfunction "1_1") (pintype "input"))
      (node (ref "R27") (pin "1") (pinfunction "1_1") (pintype "input"))
    )
    (net (code "35") (name "Net-(R26-Pad2)") (class "Default")
      (node (ref "R26") (pin "2") (pinfunction "2_2") (pintype "input"))
      (node (ref "R27") (pin "2") (pinfunction "2_2") (pintype "input"))
      (node (ref "R28") (pin "2") (pinfunction "2_2") (pintype "input"))
      (node (ref "R29") (pin "1") (pinfunction "1_1") (pintype "input"))
    )
    (net (code "36") (name "Net-(U1-USB_DM)") (class "Default")
      (node (ref "R1") (pin "2") (pinfunction "2_2") (pintype "input"))
      (node (ref "U1") (pin "46") (pinfunction "USB_DM_46") (pintype "bidirectional"))
    )
    (net (code "37") (name "Net-(U1-USB_DP)") (class "Default")
      (node (ref "R2") (pin "1") (pinfunction "1_1") (pintype "input"))
      (node (ref "U1") (pin "47") (pinfunction "USB_DP_47") (pintype "bidirectional"))
    )
    (net (code "38") (name "Net-(U4-USB_DM)") (class "Default")
      (node (ref "R6") (pin "2") (pinfunction "2_2") (pintype "input"))
      (node (ref "U4") (pin "46") (pinfunction "USB_DM_46") (pintype "bidirectional"))
    )
    (net (code "39") (name "Net-(U4-USB_DP)") (class "Default")
      (node (ref "R5") (pin "1") (pinfunction "1_1") (pintype "input"))
      (node (ref "U4") (pin "47") (pinfunction "USB_DP_47") (pintype "bidirectional"))
    )
    (net (code "40") (name "Net-(USBC2-CC1)") (class "Default")
      (node (ref "R8") (pin "2") (pinfunction "2_2") (pintype "input"))
      (node (ref "USBC2") (pin "A5") (pinfunction "CC1_A5") (pintype "unspecified"))
    )
    (net (code "41") (name "Net-(USBC2-CC2)") (class "Default")
      (node (ref "R7") (pin "1") (pinfunction "1_1") (pintype "input"))
      (node (ref "USBC2") (pin "B5") (pinfunction "CC2_B5") (pintype "unspecified"))
    )
    (net (code "42") (name "Net-(X1-OSC2)") (class "Default")
      (node (ref "C29") (pin "1") (pinfunction "1_1") (pintype "input"))
      (node (ref "R9") (pin "1") (pinfunction "1_1") (pintype "input"))
      (node (ref "X1") (pin "3") (pinfunction "OSC2_3") (pintype "unspecified"))
    )
    (net (code "43") (name "Net-(X2-OSC2)") (class "Default")
      (node (ref "C31") (pin "1") (pinfunction "1_1") (pintype "input"))
      (node (ref "R10") (pin "1") (pinfunction "1_1") (pintype "input"))
      (node (ref "X2") (pin "3") (pinfunction "OSC2_3") (pintype "unspecified"))
    )
    (net (code "44") (name "QSPI_CLK") (class "Default")
      (node (ref "U4") (pin "52") (pinfunction "QSPI_SCLK_52") (pintype "output"))
      (node (ref "U5") (pin "6") (pinfunction "CLK_6") (pintype "unspecified"))
    )
    (net (code "45") (name "QSPI_SD0") (class "Default")
      (node (ref "U4") (pin "53") (pinfunction "QSPI_SD0_53") (pintype "bidirectional"))
      (node (ref "U5") (pin "5") (pinfunction "DI_5") (pintype "unspecified"))
    )
    (net (code "46") (name "QSPI_SD1") (class "Default")
      (node (ref "U4") (pin "55") (pinfunction "QSPI_SD1_55") (pintype "bidirectional"))
      (node (ref "U5") (pin "2") (pinfunction "DO_2") (pintype "unspecified"))
    )
    (net (code "47") (name "QSPI_SD2") (class "Default")
      (node (ref "U4") (pin "54") (pinfunction "QSPI_SD2_54") (pintype "bidirectional"))
      (node (ref "U5") (pin "3") (pinfunction "IO2_3") (pintype "unspecified"))
    )
    (net (code "48") (name "QSPI_SD3") (class "Default")
      (node (ref "U4") (pin "51") (pinfunction "QSPI_SD3_51") (pintype "bidirectional"))
      (node (ref "U5") (pin "7") (pinfunction "IO3_7") (pintype "unspecified"))
    )
    (net (code "49") (name "QSPI_SS") (class "Default")
      (node (ref "R13") (pin "2") (pinfunction "2_2") (pintype "input"))
      (node (ref "R14") (pin "1") (pinfunction "1_1") (pintype "input"))
      (node (ref "U4") (pin "56") (pinfunction "QSPI_SS_56") (pintype "bidirectional"))
      (node (ref "U5") (pin "1") (pinfunction "CS#_1") (pintype "unspecified"))
    )
    (net (code "50") (name "RED") (class "Default")
      (node (ref "R22") (pin "1") (pinfunction "1_1") (pintype "input"))
      (node (ref "U4") (pin "32") (pinfunction "GPIO21_32") (pintype "bidirectional"))
    )
    (net (code "51") (name "USB_D_MINUS") (class "Default")
      (node (ref "R6") (pin "1") (pinfunction "1_1") (pintype "input"))
      (node (ref "U7") (pin "4") (pinfunction "4_4") (pintype "unspecified"))
    )
    (net (code "52") (name "USB_D_MINUS1") (class "Default")
      (node (ref "R1") (pin "1") (pinfunction "1_1") (pintype "input"))
      (node (ref "U9") (pin "4") (pinfunction "4_4") (pintype "unspecified"))
      (node (ref "USB4") (pin "2") (pinfunction "D-_2") (pintype "unspecified"))
    )
    (net (code "53") (name "USB_D_PLUS") (class "Default")
      (node (ref "R5") (pin "2") (pinfunction "2_2") (pintype "input"))
      (node (ref "U7") (pin "3") (pinfunction "3_3") (pintype "unspecified"))
    )
    (net (code "54") (name "USB_D_PLUS1") (class "Default")
      (node (ref "R2") (pin "2") (pinfunction "2_2") (pintype "input"))
      (node (ref "U9") (pin "3") (pinfunction "3_3") (pintype "unspecified"))
      (node (ref "USB4") (pin "3") (pinfunction "D+_3") (pintype "unspecified"))
    )
    (net (code "55") (name "VBUS") (class "Default")
      (node (ref "C25") (pin "2") (pinfunction "2_2") (pintype "unspecified"))
      (node (ref "C28") (pin "2") (pinfunction "2_2") (pintype "unspecified"))
      (node (ref "R18") (pin "1") (pinfunction "1_1") (pintype "input"))
      (node (ref "R21") (pin "1") (pinfunction "1_1") (pintype "input"))
      (node (ref "U11") (pin "3") (pinfunction "D_3") (pintype "unspecified"))
      (node (ref "U13") (pin "3") (pinfunction "D_3") (pintype "unspecified"))
      (node (ref "U2") (pin "3") (pinfunction "VIN_3") (pintype "unspecified"))
      (node (ref "U3") (pin "3") (pinfunction "VIN_3") (pintype "unspecified"))
      (node (ref "U7") (pin "2") (pinfunction "2_2") (pintype "unspecified"))
      (node (ref "U9") (pin "2") (pinfunction "2_2") (pintype "unspecified"))
      (node (ref "USB4") (pin "1") (pinfunction "VCC_1") (pintype "unspecified"))
      (node (ref "USBC2") (pin "A4") (pinfunction "VBUS_A4") (pintype "unspecified"))
      (node (ref "USBC2") (pin "A9") (pinfunction "VBUS_A9") (pintype "unspecified"))
      (node (ref "USBC2") (pin "B4") (pinfunction "VBUS_B4") (pintype "unspecified"))
      (node (ref "USBC2") (pin "B9") (pinfunction "VBUS_B9") (pintype "unspecified"))
    )
    (net (code "56") (name "VERTSYNC") (class "Default")
      (node (ref "DSUB1") (pin "14") (pinfunction "14_14") (pintype "unspecified"))
      (node (ref "U4") (pin "28") (pinfunction "GPIO17_28") (pintype "bidirectional"))
    )
    (net (code "57") (name "XIN") (class "Default")
      (node (ref "C30") (pin "2") (pinfunction "2_2") (pintype "input"))
      (node (ref "U4") (pin "20") (pinfunction "XIN_20") (pintype "input"))
      (node (ref "X1") (pin "1") (pinfunction "OSC1_1") (pintype "unspecified"))
    )
    (net (code "58") (name "XIN1") (class "Default")
      (node (ref "C32") (pin "2") (pinfunction "2_2") (pintype "input"))
      (node (ref "U1") (pin "20") (pinfunction "XIN_20") (pintype "input"))
      (node (ref "X2") (pin "1") (pinfunction "OSC1_1") (pintype "unspecified"))
    )
    (net (code "59") (name "XOUT") (class "Default")
      (node (ref "R9") (pin "2") (pinfunction "2_2") (pintype "input"))
      (node (ref "U4") (pin "21") (pinfunction "XOUT_21") (pintype "unspecified"))
    )
    (net (code "60") (name "XOUT1") (class "Default")
      (node (ref "R10") (pin "2") (pinfunction "2_2") (pintype "input"))
      (node (ref "U1") (pin "21") (pinfunction "XOUT_21") (pintype "unspecified"))
    )
    (net (code "61") (name "gpio8") (class "Default")
      (node (ref "R19") (pin "2") (pinfunction "2_2") (pintype "input"))
      (node (ref "U11") (pin "2") (pinfunction "S_2") (pintype "unspecified"))
      (node (ref "U4") (pin "11") (pinfunction "GPIO8_11") (pintype "bidirectional"))
    )
    (net (code "62") (name "gpio9") (class "Default")
      (node (ref "R20") (pin "2") (pinfunction "2_2") (pintype "input"))
      (node (ref "U13") (pin "2") (pinfunction "S_2") (pintype "unspecified"))
      (node (ref "U4") (pin "12") (pinfunction "GPIO9_12") (pintype "bidirectional"))
    )
    (net (code "63") (name "unconnected-(DSUB1-Pad4)") (class "Default")
      (node (ref "DSUB1") (pin "4") (pinfunction "4_4") (pintype "unspecified+no_connect"))
    )
    (net (code "64") (name "unconnected-(DSUB1-Pad9)") (class "Default")
      (node (ref "DSUB1") (pin "9") (pinfunction "9_9") (pintype "unspecified+no_connect"))
    )
    (net (code "65") (name "unconnected-(DSUB1-Pad11)") (class "Default")
      (node (ref "DSUB1") (pin "11") (pinfunction "11_11") (pintype "unspecified+no_connect"))
    )
    (net (code "66") (name "unconnected-(DSUB1-Pad12)") (class "Default")
      (node (ref "DSUB1") (pin "12") (pinfunction "12_12") (pintype "unspecified+no_connect"))
    )
    (net (code "67") (name "unconnected-(DSUB1-Pad15)") (class "Default")
      (node (ref "DSUB1") (pin "15") (pinfunction "15_15") (pintype "unspecified+no_connect"))
    )
    (net (code "68") (name "unconnected-(R25-Pad1)") (class "Default")
      (node (ref "R25") (pin "1") (pinfunction "1_1") (pintype "unspecified+no_connect"))
    )
    (net (code "69") (name "unconnected-(TF1-CD-Pad9)") (class "Default")
      (node (ref "TF1") (pin "9") (pinfunction "CD_9") (pintype "unspecified+no_connect"))
    )
    (net (code "70") (name "unconnected-(TF1-DAT1-Pad8)") (class "Default")
      (node (ref "TF1") (pin "8") (pinfunction "DAT1_8") (pintype "unspecified+no_connect"))
    )
    (net (code "71") (name "unconnected-(U1-GPIO0-Pad2)") (class "Default")
      (node (ref "U1") (pin "2") (pinfunction "GPIO0_2") (pintype "bidirectional+no_connect"))
    )
    (net (code "72") (name "unconnected-(U1-GPIO1-Pad3)") (class "Default")
      (node (ref "U1") (pin "3") (pinfunction "GPIO1_3") (pintype "bidirectional+no_connect"))
    )
    (net (code "73") (name "unconnected-(U1-GPIO2-Pad4)") (class "Default")
      (node (ref "U1") (pin "4") (pinfunction "GPIO2_4") (pintype "bidirectional+no_connect"))
    )
    (net (code "74") (name "unconnected-(U1-GPIO3-Pad5)") (class "Default")
      (node (ref "U1") (pin "5") (pinfunction "GPIO3_5") (pintype "bidirectional+no_connect"))
    )
    (net (code "75") (name "unconnected-(U1-GPIO4-Pad6)") (class "Default")
      (node (ref "U1") (pin "6") (pinfunction "GPIO4_6") (pintype "bidirectional+no_connect"))
    )
    (net (code "76") (name "unconnected-(U1-GPIO5-Pad7)") (class "Default")
      (node (ref "U1") (pin "7") (pinfunction "GPIO5_7") (pintype "bidirectional+no_connect"))
    )
    (net (code "77") (name "unconnected-(U1-GPIO6-Pad8)") (class "Default")
      (node (ref "U1") (pin "8") (pinfunction "GPIO6_8") (pintype "bidirectional+no_connect"))
    )
    (net (code "78") (name "unconnected-(U1-GPIO7-Pad9)") (class "Default")
      (node (ref "U1") (pin "9") (pinfunction "GPIO7_9") (pintype "bidirectional+no_connect"))
    )
    (net (code "79") (name "unconnected-(U1-GPIO8-Pad11)") (class "Default")
      (node (ref "U1") (pin "11") (pinfunction "GPIO8_11") (pintype "bidirectional+no_connect"))
    )
    (net (code "80") (name "unconnected-(U1-GPIO9-Pad12)") (class "Default")
      (node (ref "U1") (pin "12") (pinfunction "GPIO9_12") (pintype "bidirectional+no_connect"))
    )
    (net (code "81") (name "unconnected-(U1-GPIO10-Pad13)") (class "Default")
      (node (ref "U1") (pin "13") (pinfunction "GPIO10_13") (pintype "bidirectional+no_connect"))
    )
    (net (code "82") (name "unconnected-(U1-GPIO11-Pad14)") (class "Default")
      (node (ref "U1") (pin "14") (pinfunction "GPIO11_14") (pintype "bidirectional+no_connect"))
    )
    (net (code "83") (name "unconnected-(U1-GPIO12-Pad15)") (class "Default")
      (node (ref "U1") (pin "15") (pinfunction "GPIO12_15") (pintype "bidirectional+no_connect"))
    )
    (net (code "84") (name "unconnected-(U1-GPIO13-Pad16)") (class "Default")
      (node (ref "U1") (pin "16") (pinfunction "GPIO13_16") (pintype "bidirectional+no_connect"))
    )
    (net (code "85") (name "unconnected-(U1-GPIO18-Pad29)") (class "Default")
      (node (ref "U1") (pin "29") (pinfunction "GPIO18_29") (pintype "bidirectional+no_connect"))
    )
    (net (code "86") (name "unconnected-(U1-GPIO19-Pad30)") (class "Default")
      (node (ref "U1") (pin "30") (pinfunction "GPIO19_30") (pintype "bidirectional+no_connect"))
    )
    (net (code "87") (name "unconnected-(U1-GPIO20-Pad31)") (class "Default")
      (node (ref "U1") (pin "31") (pinfunction "GPIO20_31") (pintype "bidirectional+no_connect"))
    )
    (net (code "88") (name "unconnected-(U1-GPIO21-Pad32)") (class "Default")
      (node (ref "U1") (pin "32") (pinfunction "GPIO21_32") (pintype "bidirectional+no_connect"))
    )
    (net (code "89") (name "unconnected-(U1-GPIO22-Pad34)") (class "Default")
      (node (ref "U1") (pin "34") (pinfunction "GPIO22_34") (pintype "bidirectional+no_connect"))
    )
    (net (code "90") (name "unconnected-(U1-GPIO23-Pad35)") (class "Default")
      (node (ref "U1") (pin "35") (pinfunction "GPIO23_35") (pintype "bidirectional+no_connect"))
    )
    (net (code "91") (name "unconnected-(U1-GPIO24-Pad36)") (class "Default")
      (node (ref "U1") (pin "36") (pinfunction "GPIO24_36") (pintype "bidirectional+no_connect"))
    )
    (net (code "92") (name "unconnected-(U1-GPIO25-Pad37)") (class "Default")
      (node (ref "U1") (pin "37") (pinfunction "GPIO25_37") (pintype "bidirectional+no_connect"))
    )
    (net (code "93") (name "unconnected-(U1-GPIO26_ADC0-Pad38)") (class "Default")
      (node (ref "U1") (pin "38") (pinfunction "GPIO26_ADC0_38") (pintype "bidirectional+no_connect"))
    )
    (net (code "94") (name "unconnected-(U1-GPIO27_ADC1-Pad39)") (class "Default")
      (node (ref "U1") (pin "39") (pinfunction "GPIO27_ADC1_39") (pintype "bidirectional+no_connect"))
    )
    (net (code "95") (name "unconnected-(U1-GPIO28_ADC2-Pad40)") (class "Default")
      (node (ref "U1") (pin "40") (pinfunction "GPIO28_ADC2_40") (pintype "bidirectional+no_connect"))
    )
    (net (code "96") (name "unconnected-(U1-GPIO29_ADC3-Pad41)") (class "Default")
      (node (ref "U1") (pin "41") (pinfunction "GPIO29_ADC3_41") (pintype "bidirectional+no_connect"))
    )
    (net (code "97") (name "unconnected-(U1-RUN-Pad26)") (class "Default")
      (node (ref "U1") (pin "26") (pinfunction "RUN_26") (pintype "input+no_connect"))
    )
    (net (code "98") (name "unconnected-(U1-SWCLK-Pad24)") (class "Default")
      (node (ref "U1") (pin "24") (pinfunction "SWCLK_24") (pintype "output+no_connect"))
    )
    (net (code "99") (name "unconnected-(U1-SWD-Pad25)") (class "Default")
      (node (ref "U1") (pin "25") (pinfunction "SWD_25") (pintype "bidirectional+no_connect"))
    )
    (net (code "100") (name "unconnected-(U4-GPIO0-Pad2)") (class "Default")
      (node (ref "U4") (pin "2") (pinfunction "GPIO0_2") (pintype "bidirectional+no_connect"))
    )
    (net (code "101") (name "unconnected-(U4-GPIO1-Pad3)") (class "Default")
      (node (ref "U4") (pin "3") (pinfunction "GPIO1_3") (pintype "bidirectional+no_connect"))
    )
    (net (code "102") (name "unconnected-(U4-GPIO2-Pad4)") (class "Default")
      (node (ref "U4") (pin "4") (pinfunction "GPIO2_4") (pintype "bidirectional+no_connect"))
    )
    (net (code "103") (name "unconnected-(U4-GPIO3-Pad5)") (class "Default")
      (node (ref "U4") (pin "5") (pinfunction "GPIO3_5") (pintype "bidirectional+no_connect"))
    )
    (net (code "104") (name "unconnected-(U4-GPIO4-Pad6)") (class "Default")
      (node (ref "U4") (pin "6") (pinfunction "GPIO4_6") (pintype "bidirectional+no_connect"))
    )
    (net (code "105") (name "unconnected-(U4-GPIO5-Pad7)") (class "Default")
      (node (ref "U4") (pin "7") (pinfunction "GPIO5_7") (pintype "bidirectional+no_connect"))
    )
    (net (code "106") (name "unconnected-(U4-GPIO6-Pad8)") (class "Default")
      (node (ref "U4") (pin "8") (pinfunction "GPIO6_8") (pintype "bidirectional+no_connect"))
    )
    (net (code "107") (name "unconnected-(U4-GPIO7-Pad9)") (class "Default")
      (node (ref "U4") (pin "9") (pinfunction "GPIO7_9") (pintype "bidirectional+no_connect"))
    )
    (net (code "108") (name "unconnected-(U4-GPIO14-Pad17)") (class "Default")
      (node (ref "U4") (pin "17") (pinfunction "GPIO14_17") (pintype "bidirectional+no_connect"))
    )
    (net (code "109") (name "unconnected-(U4-GPIO15-Pad18)") (class "Default")
      (node (ref "U4") (pin "18") (pinfunction "GPIO15_18") (pintype "bidirectional+no_connect"))
    )
    (net (code "110") (name "unconnected-(U4-GPIO22-Pad34)") (class "Default")
      (node (ref "U4") (pin "34") (pinfunction "GPIO22_34") (pintype "bidirectional+no_connect"))
    )
    (net (code "111") (name "unconnected-(U4-GPIO23-Pad35)") (class "Default")
      (node (ref "U4") (pin "35") (pinfunction "GPIO23_35") (pintype "bidirectional+no_connect"))
    )
    (net (code "112") (name "unconnected-(U4-GPIO24-Pad36)") (class "Default")
      (node (ref "U4") (pin "36") (pinfunction "GPIO24_36") (pintype "bidirectional+no_connect"))
    )
    (net (code "113") (name "unconnected-(U4-GPIO25-Pad37)") (class "Default")
      (node (ref "U4") (pin "37") (pinfunction "GPIO25_37") (pintype "bidirectional+no_connect"))
    )
    (net (code "114") (name "unconnected-(U4-GPIO26_ADC0-Pad38)") (class "Default")
      (node (ref "U4") (pin "38") (pinfunction "GPIO26_ADC0_38") (pintype "bidirectional+no_connect"))
    )
    (net (code "115") (name "unconnected-(U4-GPIO27_ADC1-Pad39)") (class "Default")
      (node (ref "U4") (pin "39") (pinfunction "GPIO27_ADC1_39") (pintype "bidirectional+no_connect"))
    )
    (net (code "116") (name "unconnected-(U4-GPIO28_ADC2-Pad40)") (class "Default")
      (node (ref "U4") (pin "40") (pinfunction "GPIO28_ADC2_40") (pintype "bidirectional+no_connect"))
    )
    (net (code "117") (name "unconnected-(U4-GPIO29_ADC3-Pad41)") (class "Default")
      (node (ref "U4") (pin "41") (pinfunction "GPIO29_ADC3_41") (pintype "bidirectional+no_connect"))
    )
    (net (code "118") (name "unconnected-(U4-RUN-Pad26)") (class "Default")
      (node (ref "U4") (pin "26") (pinfunction "RUN_26") (pintype "input+no_connect"))
    )
    (net (code "119") (name "unconnected-(U4-SWCLK-Pad24)") (class "Default")
      (node (ref "U4") (pin "24") (pinfunction "SWCLK_24") (pintype "output+no_connect"))
    )
    (net (code "120") (name "unconnected-(U4-SWD-Pad25)") (class "Default")
      (node (ref "U4") (pin "25") (pinfunction "SWD_25") (pintype "bidirectional+no_connect"))
    )
    (net (code "121") (name "unconnected-(USB4-ID-Pad4)") (class "Default")
      (node (ref "USB4") (pin "4") (pinfunction "ID_4") (pintype "unspecified+no_connect"))
    )
    (net (code "122") (name "unconnected-(USBC2-DN1-PadA7)") (class "Default")
      (node (ref "USBC2") (pin "A7") (pinfunction "DN1_A7") (pintype "unspecified+no_connect"))
    )
    (net (code "123") (name "unconnected-(USBC2-DN2-PadB7)") (class "Default")
      (node (ref "USBC2") (pin "B7") (pinfunction "DN2_B7") (pintype "unspecified+no_connect"))
    )
    (net (code "124") (name "unconnected-(USBC2-DP1-PadA6)") (class "Default")
      (node (ref "USBC2") (pin "A6") (pinfunction "DP1_A6") (pintype "unspecified+no_connect"))
    )
    (net (code "125") (name "unconnected-(USBC2-DP2-PadB6)") (class "Default")
      (node (ref "USBC2") (pin "B6") (pinfunction "DP2_B6") (pintype "unspecified+no_connect"))
    )
    (net (code "126") (name "unconnected-(USBC2-SBU1-PadA8)") (class "Default")
      (node (ref "USBC2") (pin "A8") (pinfunction "SBU1_A8") (pintype "unspecified+no_connect"))
    )
    (net (code "127") (name "unconnected-(USBC2-SBU2-PadB8)") (class "Default")
      (node (ref "USBC2") (pin "B8") (pinfunction "SBU2_B8") (pintype "unspecified+no_connect"))
    )
  )
)
